# optoisolator-shield.net
KiCad netlist of a schematic drawn in EAGLE
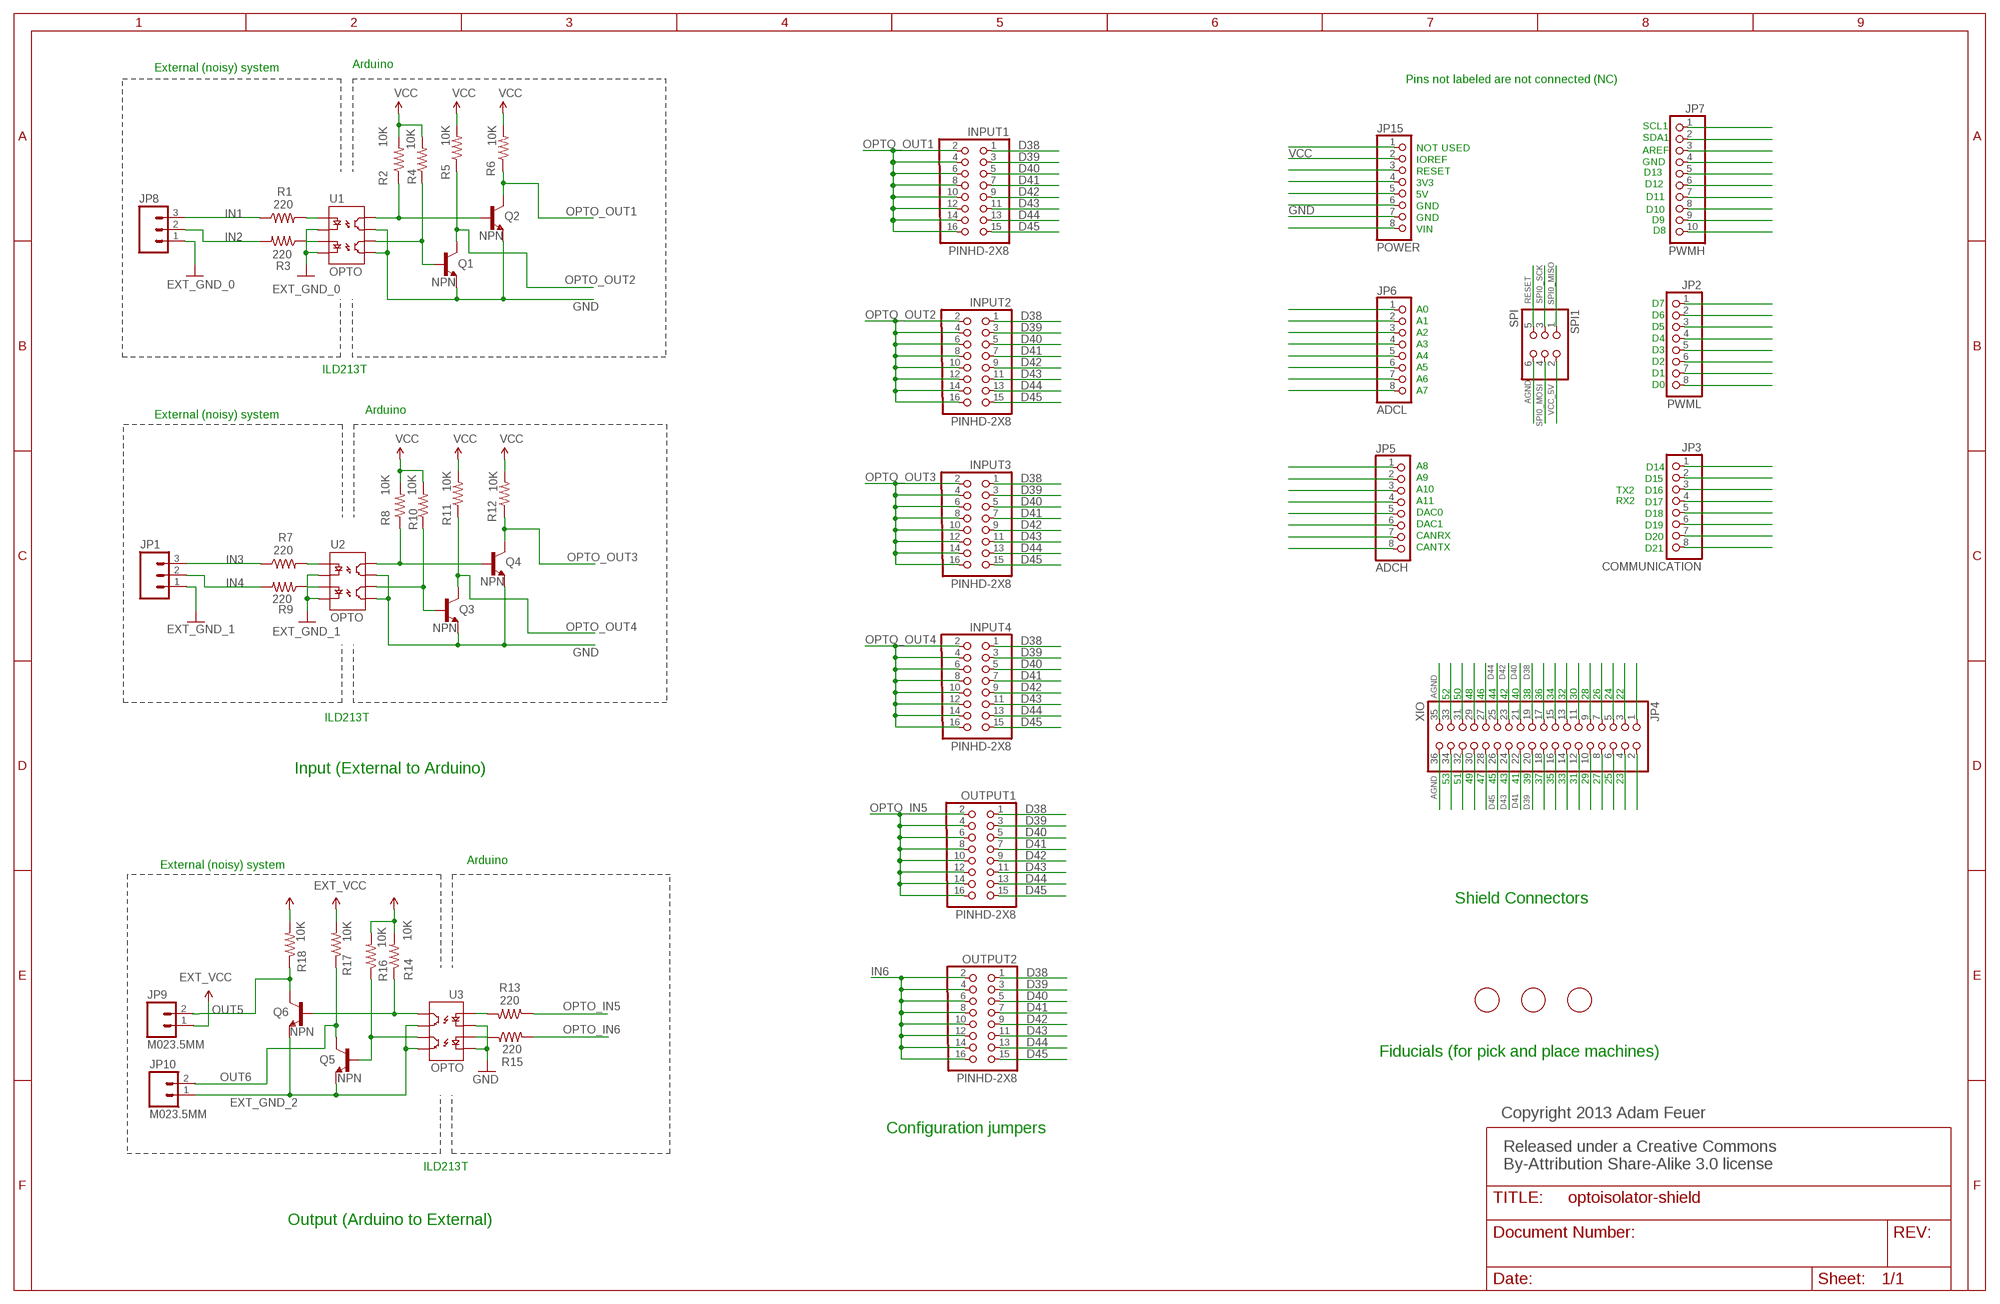
[diagram p0: schematic, sheet 1]

(export (version "E")
  (design (tool "Eeschema 10.0.6"))
  (components
    (comp (ref "INPUT1")
      (value "PINHD-2X8")
      (footprint "eagle-import:2X08")
      (libsource (lib "eagle-import") (part "PINHD-2X8"))
    )
    (comp (ref "INPUT2")
      (value "PINHD-2X8")
      (footprint "eagle-import:2X08")
      (libsource (lib "eagle-import") (part "PINHD-2X8"))
    )
    (comp (ref "INPUT3")
      (value "PINHD-2X8")
      (footprint "eagle-import:2X08")
      (libsource (lib "eagle-import") (part "PINHD-2X8"))
    )
    (comp (ref "INPUT4")
      (value "PINHD-2X8")
      (footprint "eagle-import:2X08")
      (libsource (lib "eagle-import") (part "PINHD-2X8"))
    )
    (comp (ref "JP1")
      (value "M03SCREW")
      (footprint "eagle-import:SCREWTERMINAL-3.5MM-3")
      (libsource (lib "eagle-import") (part "M03SCREW"))
    )
    (comp (ref "JP2")
      (value "PWML")
      (footprint "eagle-import:1X08")
      (libsource (lib "eagle-import") (part "PINHD-1X8"))
    )
    (comp (ref "JP3")
      (value "COMMUNICATION")
      (footprint "eagle-import:1X08")
      (libsource (lib "eagle-import") (part "PINHD-1X8"))
    )
    (comp (ref "JP4")
      (value "XIO")
      (footprint "eagle-import:2X18")
      (libsource (lib "eagle-import") (part "PINHD-2X18"))
    )
    (comp (ref "JP5")
      (value "ADCH")
      (footprint "eagle-import:1X08")
      (libsource (lib "eagle-import") (part "PINHD-1X8"))
    )
    (comp (ref "JP6")
      (value "ADCL")
      (footprint "eagle-import:1X08")
      (libsource (lib "eagle-import") (part "PINHD-1X8"))
    )
    (comp (ref "JP7")
      (value "PWMH")
      (footprint "eagle-import:1X10")
      (libsource (lib "eagle-import") (part "PINHD-1X10"))
    )
    (comp (ref "JP8")
      (value "M03SCREW")
      (footprint "eagle-import:SCREWTERMINAL-3.5MM-3")
      (libsource (lib "eagle-import") (part "M03SCREW"))
    )
    (comp (ref "JP9")
      (value "M023.5MM")
      (footprint "eagle-import:SCREWTERMINAL-3.5MM-2")
      (libsource (lib "eagle-import") (part "M023.5MM"))
    )
    (comp (ref "JP10")
      (value "M023.5MM")
      (footprint "eagle-import:SCREWTERMINAL-3.5MM-2")
      (libsource (lib "eagle-import") (part "M023.5MM"))
    )
    (comp (ref "JP15")
      (value "POWER")
      (footprint "eagle-import:1X08")
      (libsource (lib "eagle-import") (part "PINHD-1X8"))
    )
    (comp (ref "OUTPUT1")
      (value "PINHD-2X8")
      (footprint "eagle-import:2X08")
      (libsource (lib "eagle-import") (part "PINHD-2X8"))
    )
    (comp (ref "OUTPUT2")
      (value "PINHD-2X8")
      (footprint "eagle-import:2X08")
      (libsource (lib "eagle-import") (part "PINHD-2X8"))
    )
    (comp (ref "Q1")
      (value "NPN")
      (footprint "eagle-import:SOT23-3")
      (libsource (lib "eagle-import") (part "TRANSISTOR_NPNSOT23-3"))
    )
    (comp (ref "Q2")
      (value "NPN")
      (footprint "eagle-import:SOT23-3")
      (libsource (lib "eagle-import") (part "TRANSISTOR_NPNSOT23-3"))
    )
    (comp (ref "Q3")
      (value "NPN")
      (footprint "eagle-import:SOT23-3")
      (libsource (lib "eagle-import") (part "TRANSISTOR_NPNSOT23-3"))
    )
    (comp (ref "Q4")
      (value "NPN")
      (footprint "eagle-import:SOT23-3")
      (libsource (lib "eagle-import") (part "TRANSISTOR_NPNSOT23-3"))
    )
    (comp (ref "Q5")
      (value "NPN")
      (footprint "eagle-import:SOT23-3")
      (libsource (lib "eagle-import") (part "TRANSISTOR_NPNSOT23-3"))
    )
    (comp (ref "Q6")
      (value "NPN")
      (footprint "eagle-import:SOT23-3")
      (libsource (lib "eagle-import") (part "TRANSISTOR_NPNSOT23-3"))
    )
    (comp (ref "R1")
      (value "220")
      (footprint "eagle-import:C0402")
      (libsource (lib "eagle-import") (part "RESISTOR0402"))
    )
    (comp (ref "R2")
      (value "10K")
      (footprint "eagle-import:C0402")
      (libsource (lib "eagle-import") (part "RESISTOR0402"))
    )
    (comp (ref "R3")
      (value "220")
      (footprint "eagle-import:C0402")
      (libsource (lib "eagle-import") (part "RESISTOR0402"))
    )
    (comp (ref "R4")
      (value "10K")
      (footprint "eagle-import:C0402")
      (libsource (lib "eagle-import") (part "RESISTOR0402"))
    )
    (comp (ref "R5")
      (value "10K")
      (footprint "eagle-import:C0402")
      (libsource (lib "eagle-import") (part "RESISTOR0402"))
    )
    (comp (ref "R6")
      (value "10K")
      (footprint "eagle-import:C0402")
      (libsource (lib "eagle-import") (part "RESISTOR0402"))
    )
    (comp (ref "R7")
      (value "220")
      (footprint "eagle-import:C0402")
      (libsource (lib "eagle-import") (part "RESISTOR0402"))
    )
    (comp (ref "R8")
      (value "10K")
      (footprint "eagle-import:C0402")
      (libsource (lib "eagle-import") (part "RESISTOR0402"))
    )
    (comp (ref "R9")
      (value "220")
      (footprint "eagle-import:C0402")
      (libsource (lib "eagle-import") (part "RESISTOR0402"))
    )
    (comp (ref "R10")
      (value "10K")
      (footprint "eagle-import:C0402")
      (libsource (lib "eagle-import") (part "RESISTOR0402"))
    )
    (comp (ref "R11")
      (value "10K")
      (footprint "eagle-import:C0402")
      (libsource (lib "eagle-import") (part "RESISTOR0402"))
    )
    (comp (ref "R12")
      (value "10K")
      (footprint "eagle-import:C0402")
      (libsource (lib "eagle-import") (part "RESISTOR0402"))
    )
    (comp (ref "R13")
      (value "220")
      (footprint "eagle-import:C0402")
      (libsource (lib "eagle-import") (part "RESISTOR0402"))
    )
    (comp (ref "R14")
      (value "10K")
      (footprint "eagle-import:C0402")
      (libsource (lib "eagle-import") (part "RESISTOR0402"))
    )
    (comp (ref "R15")
      (value "220")
      (footprint "eagle-import:C0402")
      (libsource (lib "eagle-import") (part "RESISTOR0402"))
    )
    (comp (ref "R16")
      (value "10K")
      (footprint "eagle-import:C0402")
      (libsource (lib "eagle-import") (part "RESISTOR0402"))
    )
    (comp (ref "R17")
      (value "10K")
      (footprint "eagle-import:C0402")
      (libsource (lib "eagle-import") (part "RESISTOR0402"))
    )
    (comp (ref "R18")
      (value "10K")
      (footprint "eagle-import:C0402")
      (libsource (lib "eagle-import") (part "RESISTOR0402"))
    )
    (comp (ref "SPI1")
      (value "SPI")
      (footprint "eagle-import:2X03")
      (libsource (lib "eagle-import") (part "PINHD-2X3"))
    )
    (comp (ref "U$2")
      (value "FIDUCIAL")
      (footprint "eagle-import:FIDUCIAL_1MM")
      (libsource (lib "eagle-import") (part "FIDUCIAL"))
    )
    (comp (ref "U$5")
      (value "FIDUCIAL")
      (footprint "eagle-import:FIDUCIAL_1MM")
      (libsource (lib "eagle-import") (part "FIDUCIAL"))
    )
    (comp (ref "U$6")
      (value "FIDUCIAL")
      (footprint "eagle-import:FIDUCIAL_1MM")
      (libsource (lib "eagle-import") (part "FIDUCIAL"))
    )
    (comp (ref "U1")
      (value "OPTO")
      (footprint "eagle-import:SO08-2")
      (libsource (lib "eagle-import") (part "OPTOISOLATOR-2SOIC8"))
    )
    (comp (ref "U2")
      (value "OPTO")
      (footprint "eagle-import:SO08-2")
      (libsource (lib "eagle-import") (part "OPTOISOLATOR-2SOIC8"))
    )
    (comp (ref "U3")
      (value "OPTO")
      (footprint "eagle-import:SO08-2")
      (libsource (lib "eagle-import") (part "OPTOISOLATOR-2SOIC8"))
    )
  )
  (nets
    (net (code "1") (name "/AGND") (class "Default")
      (node (ref "JP4") (pin "35") (pinfunction "35_35") (pintype "passive"))
      (node (ref "JP4") (pin "36") (pinfunction "36_36") (pintype "passive"))
      (node (ref "SPI1") (pin "6") (pinfunction "6_6") (pintype "passive"))
    )
    (net (code "2") (name "/D38") (class "Default")
      (node (ref "INPUT1") (pin "1") (pinfunction "1_1") (pintype "passive"))
      (node (ref "INPUT2") (pin "1") (pinfunction "1_1") (pintype "passive"))
      (node (ref "INPUT3") (pin "1") (pinfunction "1_1") (pintype "passive"))
      (node (ref "INPUT4") (pin "1") (pinfunction "1_1") (pintype "passive"))
      (node (ref "JP4") (pin "19") (pinfunction "19_19") (pintype "passive"))
      (node (ref "OUTPUT1") (pin "1") (pinfunction "1_1") (pintype "passive"))
      (node (ref "OUTPUT2") (pin "1") (pinfunction "1_1") (pintype "passive"))
    )
    (net (code "3") (name "/D39") (class "Default")
      (node (ref "INPUT1") (pin "3") (pinfunction "3_3") (pintype "passive"))
      (node (ref "INPUT2") (pin "3") (pinfunction "3_3") (pintype "passive"))
      (node (ref "INPUT3") (pin "3") (pinfunction "3_3") (pintype "passive"))
      (node (ref "INPUT4") (pin "3") (pinfunction "3_3") (pintype "passive"))
      (node (ref "JP4") (pin "20") (pinfunction "20_20") (pintype "passive"))
      (node (ref "OUTPUT1") (pin "3") (pinfunction "3_3") (pintype "passive"))
      (node (ref "OUTPUT2") (pin "3") (pinfunction "3_3") (pintype "passive"))
    )
    (net (code "4") (name "/D40") (class "Default")
      (node (ref "INPUT1") (pin "5") (pinfunction "5_5") (pintype "passive"))
      (node (ref "INPUT2") (pin "5") (pinfunction "5_5") (pintype "passive"))
      (node (ref "INPUT3") (pin "5") (pinfunction "5_5") (pintype "passive"))
      (node (ref "INPUT4") (pin "5") (pinfunction "5_5") (pintype "passive"))
      (node (ref "JP4") (pin "21") (pinfunction "21_21") (pintype "passive"))
      (node (ref "OUTPUT1") (pin "5") (pinfunction "5_5") (pintype "passive"))
      (node (ref "OUTPUT2") (pin "5") (pinfunction "5_5") (pintype "passive"))
    )
    (net (code "5") (name "/D41") (class "Default")
      (node (ref "INPUT1") (pin "7") (pinfunction "7_7") (pintype "passive"))
      (node (ref "INPUT2") (pin "7") (pinfunction "7_7") (pintype "passive"))
      (node (ref "INPUT3") (pin "7") (pinfunction "7_7") (pintype "passive"))
      (node (ref "INPUT4") (pin "7") (pinfunction "7_7") (pintype "passive"))
      (node (ref "JP4") (pin "22") (pinfunction "22_22") (pintype "passive"))
      (node (ref "OUTPUT1") (pin "7") (pinfunction "7_7") (pintype "passive"))
      (node (ref "OUTPUT2") (pin "7") (pinfunction "7_7") (pintype "passive"))
    )
    (net (code "6") (name "/D42") (class "Default")
      (node (ref "INPUT1") (pin "9") (pinfunction "9_9") (pintype "passive"))
      (node (ref "INPUT2") (pin "9") (pinfunction "9_9") (pintype "passive"))
      (node (ref "INPUT3") (pin "9") (pinfunction "9_9") (pintype "passive"))
      (node (ref "INPUT4") (pin "9") (pinfunction "9_9") (pintype "passive"))
      (node (ref "JP4") (pin "23") (pinfunction "23_23") (pintype "passive"))
      (node (ref "OUTPUT1") (pin "9") (pinfunction "9_9") (pintype "passive"))
      (node (ref "OUTPUT2") (pin "9") (pinfunction "9_9") (pintype "passive"))
    )
    (net (code "7") (name "/D43") (class "Default")
      (node (ref "INPUT1") (pin "11") (pinfunction "11_11") (pintype "passive"))
      (node (ref "INPUT2") (pin "11") (pinfunction "11_11") (pintype "passive"))
      (node (ref "INPUT3") (pin "11") (pinfunction "11_11") (pintype "passive"))
      (node (ref "INPUT4") (pin "11") (pinfunction "11_11") (pintype "passive"))
      (node (ref "JP4") (pin "24") (pinfunction "24_24") (pintype "passive"))
      (node (ref "OUTPUT1") (pin "11") (pinfunction "11_11") (pintype "passive"))
      (node (ref "OUTPUT2") (pin "11") (pinfunction "11_11") (pintype "passive"))
    )
    (net (code "8") (name "/D44") (class "Default")
      (node (ref "INPUT1") (pin "13") (pinfunction "13_13") (pintype "passive"))
      (node (ref "INPUT2") (pin "13") (pinfunction "13_13") (pintype "passive"))
      (node (ref "INPUT3") (pin "13") (pinfunction "13_13") (pintype "passive"))
      (node (ref "INPUT4") (pin "13") (pinfunction "13_13") (pintype "passive"))
      (node (ref "JP4") (pin "25") (pinfunction "25_25") (pintype "passive"))
      (node (ref "OUTPUT1") (pin "13") (pinfunction "13_13") (pintype "passive"))
      (node (ref "OUTPUT2") (pin "13") (pinfunction "13_13") (pintype "passive"))
    )
    (net (code "9") (name "/D45") (class "Default")
      (node (ref "INPUT1") (pin "15") (pinfunction "15_15") (pintype "passive"))
      (node (ref "INPUT2") (pin "15") (pinfunction "15_15") (pintype "passive"))
      (node (ref "INPUT3") (pin "15") (pinfunction "15_15") (pintype "passive"))
      (node (ref "INPUT4") (pin "15") (pinfunction "15_15") (pintype "passive"))
      (node (ref "JP4") (pin "26") (pinfunction "26_26") (pintype "passive"))
      (node (ref "OUTPUT1") (pin "15") (pinfunction "15_15") (pintype "passive"))
      (node (ref "OUTPUT2") (pin "15") (pinfunction "15_15") (pintype "passive"))
    )
    (net (code "10") (name "/EXT_GND_2") (class "Default")
      (node (ref "JP10") (pin "1") (pinfunction "1_1") (pintype "passive"))
      (node (ref "Q5") (pin "2") (pinfunction "E_2") (pintype "passive"))
      (node (ref "Q6") (pin "2") (pinfunction "E_2") (pintype "passive"))
      (node (ref "U3") (pin "5") (pinfunction "EM2_5") (pintype "bidirectional"))
      (node (ref "U3") (pin "7") (pinfunction "EM1_7") (pintype "bidirectional"))
    )
    (net (code "11") (name "/IN1") (class "Default")
      (node (ref "JP8") (pin "3") (pinfunction "3_3") (pintype "passive"))
      (node (ref "R1") (pin "1") (pinfunction "1_1") (pintype "passive"))
    )
    (net (code "12") (name "/IN2") (class "Default")
      (node (ref "JP8") (pin "2") (pinfunction "2_2") (pintype "passive"))
      (node (ref "R3") (pin "2") (pinfunction "2_2") (pintype "passive"))
    )
    (net (code "13") (name "/IN3") (class "Default")
      (node (ref "JP1") (pin "3") (pinfunction "3_3") (pintype "passive"))
      (node (ref "R7") (pin "1") (pinfunction "1_1") (pintype "passive"))
    )
    (net (code "14") (name "/IN4") (class "Default")
      (node (ref "JP1") (pin "2") (pinfunction "2_2") (pintype "passive"))
      (node (ref "R9") (pin "2") (pinfunction "2_2") (pintype "passive"))
    )
    (net (code "15") (name "/IN6") (class "Default")
      (node (ref "OUTPUT2") (pin "10") (pinfunction "10_10") (pintype "passive"))
      (node (ref "OUTPUT2") (pin "12") (pinfunction "12_12") (pintype "passive"))
      (node (ref "OUTPUT2") (pin "14") (pinfunction "14_14") (pintype "passive"))
      (node (ref "OUTPUT2") (pin "16") (pinfunction "16_16") (pintype "passive"))
      (node (ref "OUTPUT2") (pin "2") (pinfunction "2_2") (pintype "passive"))
      (node (ref "OUTPUT2") (pin "4") (pinfunction "4_4") (pintype "passive"))
      (node (ref "OUTPUT2") (pin "6") (pinfunction "6_6") (pintype "passive"))
      (node (ref "OUTPUT2") (pin "8") (pinfunction "8_8") (pintype "passive"))
    )
    (net (code "16") (name "/OPTO_IN5") (class "Default")
      (node (ref "OUTPUT1") (pin "10") (pinfunction "10_10") (pintype "passive"))
      (node (ref "OUTPUT1") (pin "12") (pinfunction "12_12") (pintype "passive"))
      (node (ref "OUTPUT1") (pin "14") (pinfunction "14_14") (pintype "passive"))
      (node (ref "OUTPUT1") (pin "16") (pinfunction "16_16") (pintype "passive"))
      (node (ref "OUTPUT1") (pin "2") (pinfunction "2_2") (pintype "passive"))
      (node (ref "OUTPUT1") (pin "4") (pinfunction "4_4") (pintype "passive"))
      (node (ref "OUTPUT1") (pin "6") (pinfunction "6_6") (pintype "passive"))
      (node (ref "OUTPUT1") (pin "8") (pinfunction "8_8") (pintype "passive"))
      (node (ref "R13") (pin "1") (pinfunction "1_1") (pintype "passive"))
    )
    (net (code "17") (name "/OPTO_IN6") (class "Default")
      (node (ref "R15") (pin "2") (pinfunction "2_2") (pintype "passive"))
    )
    (net (code "18") (name "/OPTO_OUT1") (class "Default")
      (node (ref "INPUT1") (pin "10") (pinfunction "10_10") (pintype "passive"))
      (node (ref "INPUT1") (pin "12") (pinfunction "12_12") (pintype "passive"))
      (node (ref "INPUT1") (pin "14") (pinfunction "14_14") (pintype "passive"))
      (node (ref "INPUT1") (pin "16") (pinfunction "16_16") (pintype "passive"))
      (node (ref "INPUT1") (pin "2") (pinfunction "2_2") (pintype "passive"))
      (node (ref "INPUT1") (pin "4") (pinfunction "4_4") (pintype "passive"))
      (node (ref "INPUT1") (pin "6") (pinfunction "6_6") (pintype "passive"))
      (node (ref "INPUT1") (pin "8") (pinfunction "8_8") (pintype "passive"))
      (node (ref "Q2") (pin "3") (pinfunction "C_3") (pintype "passive"))
      (node (ref "R6") (pin "1") (pinfunction "1_1") (pintype "passive"))
    )
    (net (code "19") (name "/OPTO_OUT2") (class "Default")
      (node (ref "INPUT2") (pin "10") (pinfunction "10_10") (pintype "passive"))
      (node (ref "INPUT2") (pin "12") (pinfunction "12_12") (pintype "passive"))
      (node (ref "INPUT2") (pin "14") (pinfunction "14_14") (pintype "passive"))
      (node (ref "INPUT2") (pin "16") (pinfunction "16_16") (pintype "passive"))
      (node (ref "INPUT2") (pin "2") (pinfunction "2_2") (pintype "passive"))
      (node (ref "INPUT2") (pin "4") (pinfunction "4_4") (pintype "passive"))
      (node (ref "INPUT2") (pin "6") (pinfunction "6_6") (pintype "passive"))
      (node (ref "INPUT2") (pin "8") (pinfunction "8_8") (pintype "passive"))
      (node (ref "Q1") (pin "3") (pinfunction "C_3") (pintype "passive"))
      (node (ref "R5") (pin "1") (pinfunction "1_1") (pintype "passive"))
    )
    (net (code "20") (name "/OPTO_OUT3") (class "Default")
      (node (ref "INPUT3") (pin "10") (pinfunction "10_10") (pintype "passive"))
      (node (ref "INPUT3") (pin "12") (pinfunction "12_12") (pintype "passive"))
      (node (ref "INPUT3") (pin "14") (pinfunction "14_14") (pintype "passive"))
      (node (ref "INPUT3") (pin "16") (pinfunction "16_16") (pintype "passive"))
      (node (ref "INPUT3") (pin "2") (pinfunction "2_2") (pintype "passive"))
      (node (ref "INPUT3") (pin "4") (pinfunction "4_4") (pintype "passive"))
      (node (ref "INPUT3") (pin "6") (pinfunction "6_6") (pintype "passive"))
      (node (ref "INPUT3") (pin "8") (pinfunction "8_8") (pintype "passive"))
      (node (ref "Q4") (pin "3") (pinfunction "C_3") (pintype "passive"))
      (node (ref "R12") (pin "1") (pinfunction "1_1") (pintype "passive"))
    )
    (net (code "21") (name "/OPTO_OUT4") (class "Default")
      (node (ref "INPUT4") (pin "10") (pinfunction "10_10") (pintype "passive"))
      (node (ref "INPUT4") (pin "12") (pinfunction "12_12") (pintype "passive"))
      (node (ref "INPUT4") (pin "14") (pinfunction "14_14") (pintype "passive"))
      (node (ref "INPUT4") (pin "16") (pinfunction "16_16") (pintype "passive"))
      (node (ref "INPUT4") (pin "2") (pinfunction "2_2") (pintype "passive"))
      (node (ref "INPUT4") (pin "4") (pinfunction "4_4") (pintype "passive"))
      (node (ref "INPUT4") (pin "6") (pinfunction "6_6") (pintype "passive"))
      (node (ref "INPUT4") (pin "8") (pinfunction "8_8") (pintype "passive"))
      (node (ref "Q3") (pin "3") (pinfunction "C_3") (pintype "passive"))
      (node (ref "R11") (pin "1") (pinfunction "1_1") (pintype "passive"))
    )
    (net (code "22") (name "/OUT5") (class "Default")
      (node (ref "Q6") (pin "3") (pinfunction "C_3") (pintype "passive"))
      (node (ref "R18") (pin "1") (pinfunction "1_1") (pintype "passive"))
    )
    (net (code "23") (name "/OUT6") (class "Default")
      (node (ref "Q5") (pin "3") (pinfunction "C_3") (pintype "passive"))
      (node (ref "R17") (pin "1") (pinfunction "1_1") (pintype "passive"))
    )
    (net (code "24") (name "/RESET") (class "Default")
      (node (ref "SPI1") (pin "5") (pinfunction "5_5") (pintype "passive"))
    )
    (net (code "25") (name "/SPI0_MISO") (class "Default")
      (node (ref "SPI1") (pin "1") (pinfunction "1_1") (pintype "passive"))
    )
    (net (code "26") (name "/SPI0_MOSI") (class "Default")
      (node (ref "SPI1") (pin "4") (pinfunction "4_4") (pintype "passive"))
    )
    (net (code "27") (name "/SPI0_SCK") (class "Default")
      (node (ref "SPI1") (pin "3") (pinfunction "3_3") (pintype "passive"))
    )
    (net (code "28") (name "/VCC_5V") (class "Default")
      (node (ref "SPI1") (pin "2") (pinfunction "2_2") (pintype "passive"))
    )
    (net (code "29") (name "EXTERNAL_VCC") (class "Default")
      (node (ref "JP9") (pin "1") (pinfunction "1_1") (pintype "passive"))
      (node (ref "R14") (pin "2") (pinfunction "2_2") (pintype "passive"))
      (node (ref "R16") (pin "2") (pinfunction "2_2") (pintype "passive"))
      (node (ref "R17") (pin "2") (pinfunction "2_2") (pintype "passive"))
      (node (ref "R18") (pin "2") (pinfunction "2_2") (pintype "passive"))
    )
    (net (code "30") (name "EXT_GND_0") (class "Default")
      (node (ref "JP8") (pin "1") (pinfunction "1_1") (pintype "passive"))
      (node (ref "U1") (pin "2") (pinfunction "C1_2") (pintype "bidirectional"))
      (node (ref "U1") (pin "4") (pinfunction "C2_4") (pintype "bidirectional"))
    )
    (net (code "31") (name "EXT_GND_1") (class "Default")
      (node (ref "JP1") (pin "1") (pinfunction "1_1") (pintype "passive"))
      (node (ref "U2") (pin "2") (pinfunction "C1_2") (pintype "bidirectional"))
      (node (ref "U2") (pin "4") (pinfunction "C2_4") (pintype "bidirectional"))
    )
    (net (code "32") (name "GND") (class "Default")
      (node (ref "JP15") (pin "7") (pinfunction "7_7") (pintype "passive"))
      (node (ref "Q1") (pin "2") (pinfunction "E_2") (pintype "passive"))
      (node (ref "Q2") (pin "2") (pinfunction "E_2") (pintype "passive"))
      (node (ref "Q3") (pin "2") (pinfunction "E_2") (pintype "passive"))
      (node (ref "Q4") (pin "2") (pinfunction "E_2") (pintype "passive"))
      (node (ref "U1") (pin "5") (pinfunction "EM2_5") (pintype "bidirectional"))
      (node (ref "U1") (pin "7") (pinfunction "EM1_7") (pintype "bidirectional"))
      (node (ref "U2") (pin "5") (pinfunction "EM2_5") (pintype "bidirectional"))
      (node (ref "U2") (pin "7") (pinfunction "EM1_7") (pintype "bidirectional"))
      (node (ref "U3") (pin "2") (pinfunction "C1_2") (pintype "bidirectional"))
      (node (ref "U3") (pin "4") (pinfunction "C2_4") (pintype "bidirectional"))
    )
    (net (code "33") (name "Net-(Q1-B)") (class "Default")
      (node (ref "Q1") (pin "1") (pinfunction "B_1") (pintype "passive"))
      (node (ref "R4") (pin "1") (pinfunction "1_1") (pintype "passive"))
      (node (ref "U1") (pin "6") (pinfunction "CL2_6") (pintype "bidirectional"))
    )
    (net (code "34") (name "Net-(Q2-B)") (class "Default")
      (node (ref "Q2") (pin "1") (pinfunction "B_1") (pintype "passive"))
      (node (ref "R2") (pin "1") (pinfunction "1_1") (pintype "passive"))
      (node (ref "U1") (pin "8") (pinfunction "CL1_8") (pintype "bidirectional"))
    )
    (net (code "35") (name "Net-(Q3-B)") (class "Default")
      (node (ref "Q3") (pin "1") (pinfunction "B_1") (pintype "passive"))
      (node (ref "R10") (pin "1") (pinfunction "1_1") (pintype "passive"))
      (node (ref "U2") (pin "6") (pinfunction "CL2_6") (pintype "bidirectional"))
    )
    (net (code "36") (name "Net-(Q4-B)") (class "Default")
      (node (ref "Q4") (pin "1") (pinfunction "B_1") (pintype "passive"))
      (node (ref "R8") (pin "1") (pinfunction "1_1") (pintype "passive"))
      (node (ref "U2") (pin "8") (pinfunction "CL1_8") (pintype "bidirectional"))
    )
    (net (code "37") (name "Net-(Q5-B)") (class "Default")
      (node (ref "Q5") (pin "1") (pinfunction "B_1") (pintype "passive"))
      (node (ref "R16") (pin "1") (pinfunction "1_1") (pintype "passive"))
      (node (ref "U3") (pin "6") (pinfunction "CL2_6") (pintype "bidirectional"))
    )
    (net (code "38") (name "Net-(Q6-B)") (class "Default")
      (node (ref "Q6") (pin "1") (pinfunction "B_1") (pintype "passive"))
      (node (ref "R14") (pin "1") (pinfunction "1_1") (pintype "passive"))
      (node (ref "U3") (pin "8") (pinfunction "CL1_8") (pintype "bidirectional"))
    )
    (net (code "39") (name "Net-(U1-A1)") (class "Default")
      (node (ref "R1") (pin "2") (pinfunction "2_2") (pintype "passive"))
      (node (ref "U1") (pin "1") (pinfunction "A1_1") (pintype "bidirectional"))
    )
    (net (code "40") (name "Net-(U1-A2)") (class "Default")
      (node (ref "R3") (pin "1") (pinfunction "1_1") (pintype "passive"))
      (node (ref "U1") (pin "3") (pinfunction "A2_3") (pintype "bidirectional"))
    )
    (net (code "41") (name "Net-(U2-A1)") (class "Default")
      (node (ref "R7") (pin "2") (pinfunction "2_2") (pintype "passive"))
      (node (ref "U2") (pin "1") (pinfunction "A1_1") (pintype "bidirectional"))
    )
    (net (code "42") (name "Net-(U2-A2)") (class "Default")
      (node (ref "R9") (pin "1") (pinfunction "1_1") (pintype "passive"))
      (node (ref "U2") (pin "3") (pinfunction "A2_3") (pintype "bidirectional"))
    )
    (net (code "43") (name "Net-(U3-A1)") (class "Default")
      (node (ref "R13") (pin "2") (pinfunction "2_2") (pintype "passive"))
      (node (ref "U3") (pin "1") (pinfunction "A1_1") (pintype "bidirectional"))
    )
    (net (code "44") (name "Net-(U3-A2)") (class "Default")
      (node (ref "R15") (pin "1") (pinfunction "1_1") (pintype "passive"))
      (node (ref "U3") (pin "3") (pinfunction "A2_3") (pintype "bidirectional"))
    )
    (net (code "45") (name "VCC") (class "Default")
      (node (ref "JP15") (pin "2") (pinfunction "2_2") (pintype "passive"))
      (node (ref "R10") (pin "2") (pinfunction "2_2") (pintype "passive"))
      (node (ref "R11") (pin "2") (pinfunction "2_2") (pintype "passive"))
      (node (ref "R12") (pin "2") (pinfunction "2_2") (pintype "passive"))
      (node (ref "R2") (pin "2") (pinfunction "2_2") (pintype "passive"))
      (node (ref "R4") (pin "2") (pinfunction "2_2") (pintype "passive"))
      (node (ref "R5") (pin "2") (pinfunction "2_2") (pintype "passive"))
      (node (ref "R6") (pin "2") (pinfunction "2_2") (pintype "passive"))
      (node (ref "R8") (pin "2") (pinfunction "2_2") (pintype "passive"))
    )
    (net (code "46") (name "unconnected-(JP2-Pad1)") (class "Default")
      (node (ref "JP2") (pin "1") (pinfunction "1_1") (pintype "passive"))
    )
    (net (code "47") (name "unconnected-(JP2-Pad2)") (class "Default")
      (node (ref "JP2") (pin "2") (pinfunction "2_2") (pintype "passive"))
    )
    (net (code "48") (name "unconnected-(JP2-Pad3)") (class "Default")
      (node (ref "JP2") (pin "3") (pinfunction "3_3") (pintype "passive"))
    )
    (net (code "49") (name "unconnected-(JP2-Pad4)") (class "Default")
      (node (ref "JP2") (pin "4") (pinfunction "4_4") (pintype "passive"))
    )
    (net (code "50") (name "unconnected-(JP2-Pad5)") (class "Default")
      (node (ref "JP2") (pin "5") (pinfunction "5_5") (pintype "passive"))
    )
    (net (code "51") (name "unconnected-(JP2-Pad6)") (class "Default")
      (node (ref "JP2") (pin "6") (pinfunction "6_6") (pintype "passive"))
    )
    (net (code "52") (name "unconnected-(JP2-Pad7)") (class "Default")
      (node (ref "JP2") (pin "7") (pinfunction "7_7") (pintype "passive"))
    )
    (net (code "53") (name "unconnected-(JP2-Pad8)") (class "Default")
      (node (ref "JP2") (pin "8") (pinfunction "8_8") (pintype "passive"))
    )
    (net (code "54") (name "unconnected-(JP3-Pad1)") (class "Default")
      (node (ref "JP3") (pin "1") (pinfunction "1_1") (pintype "passive"))
    )
    (net (code "55") (name "unconnected-(JP3-Pad2)") (class "Default")
      (node (ref "JP3") (pin "2") (pinfunction "2_2") (pintype "passive"))
    )
    (net (code "56") (name "unconnected-(JP3-Pad3)") (class "Default")
      (node (ref "JP3") (pin "3") (pinfunction "3_3") (pintype "passive"))
    )
    (net (code "57") (name "unconnected-(JP3-Pad4)") (class "Default")
      (node (ref "JP3") (pin "4") (pinfunction "4_4") (pintype "passive"))
    )
    (net (code "58") (name "unconnected-(JP3-Pad5)") (class "Default")
      (node (ref "JP3") (pin "5") (pinfunction "5_5") (pintype "passive"))
    )
    (net (code "59") (name "unconnected-(JP3-Pad6)") (class "Default")
      (node (ref "JP3") (pin "6") (pinfunction "6_6") (pintype "passive"))
    )
    (net (code "60") (name "unconnected-(JP3-Pad7)") (class "Default")
      (node (ref "JP3") (pin "7") (pinfunction "7_7") (pintype "passive"))
    )
    (net (code "61") (name "unconnected-(JP3-Pad8)") (class "Default")
      (node (ref "JP3") (pin "8") (pinfunction "8_8") (pintype "passive"))
    )
    (net (code "62") (name "unconnected-(JP4-Pad1)") (class "Default")
      (node (ref "JP4") (pin "1") (pinfunction "1_1") (pintype "passive"))
    )
    (net (code "63") (name "unconnected-(JP4-Pad2)") (class "Default")
      (node (ref "JP4") (pin "2") (pinfunction "2_2") (pintype "passive"))
    )
    (net (code "64") (name "unconnected-(JP4-Pad3)") (class "Default")
      (node (ref "JP4") (pin "3") (pinfunction "3_3") (pintype "passive"))
    )
    (net (code "65") (name "unconnected-(JP4-Pad4)") (class "Default")
      (node (ref "JP4") (pin "4") (pinfunction "4_4") (pintype "passive"))
    )
    (net (code "66") (name "unconnected-(JP4-Pad5)") (class "Default")
      (node (ref "JP4") (pin "5") (pinfunction "5_5") (pintype "passive"))
    )
    (net (code "67") (name "unconnected-(JP4-Pad6)") (class "Default")
      (node (ref "JP4") (pin "6") (pinfunction "6_6") (pintype "passive"))
    )
    (net (code "68") (name "unconnected-(JP4-Pad7)") (class "Default")
      (node (ref "JP4") (pin "7") (pinfunction "7_7") (pintype "passive"))
    )
    (net (code "69") (name "unconnected-(JP4-Pad8)") (class "Default")
      (node (ref "JP4") (pin "8") (pinfunction "8_8") (pintype "passive"))
    )
    (net (code "70") (name "unconnected-(JP4-Pad9)") (class "Default")
      (node (ref "JP4") (pin "9") (pinfunction "9_9") (pintype "passive"))
    )
    (net (code "71") (name "unconnected-(JP4-Pad10)") (class "Default")
      (node (ref "JP4") (pin "10") (pinfunction "10_10") (pintype "passive"))
    )
    (net (code "72") (name "unconnected-(JP4-Pad11)") (class "Default")
      (node (ref "JP4") (pin "11") (pinfunction "11_11") (pintype "passive"))
    )
    (net (code "73") (name "unconnected-(JP4-Pad12)") (class "Default")
      (node (ref "JP4") (pin "12") (pinfunction "12_12") (pintype "passive"))
    )
    (net (code "74") (name "unconnected-(JP4-Pad13)") (class "Default")
      (node (ref "JP4") (pin "13") (pinfunction "13_13") (pintype "passive"))
    )
    (net (code "75") (name "unconnected-(JP4-Pad14)") (class "Default")
      (node (ref "JP4") (pin "14") (pinfunction "14_14") (pintype "passive"))
    )
    (net (code "76") (name "unconnected-(JP4-Pad15)") (class "Default")
      (node (ref "JP4") (pin "15") (pinfunction "15_15") (pintype "passive"))
    )
    (net (code "77") (name "unconnected-(JP4-Pad16)") (class "Default")
      (node (ref "JP4") (pin "16") (pinfunction "16_16") (pintype "passive"))
    )
    (net (code "78") (name "unconnected-(JP4-Pad17)") (class "Default")
      (node (ref "JP4") (pin "17") (pinfunction "17_17") (pintype "passive"))
    )
    (net (code "79") (name "unconnected-(JP4-Pad18)") (class "Default")
      (node (ref "JP4") (pin "18") (pinfunction "18_18") (pintype "passive"))
    )
    (net (code "80") (name "unconnected-(JP4-Pad27)") (class "Default")
      (node (ref "JP4") (pin "27") (pinfunction "27_27") (pintype "passive"))
    )
    (net (code "81") (name "unconnected-(JP4-Pad28)") (class "Default")
      (node (ref "JP4") (pin "28") (pinfunction "28_28") (pintype "passive"))
    )
    (net (code "82") (name "unconnected-(JP4-Pad29)") (class "Default")
      (node (ref "JP4") (pin "29") (pinfunction "29_29") (pintype "passive"))
    )
    (net (code "83") (name "unconnected-(JP4-Pad30)") (class "Default")
      (node (ref "JP4") (pin "30") (pinfunction "30_30") (pintype "passive"))
    )
    (net (code "84") (name "unconnected-(JP4-Pad31)") (class "Default")
      (node (ref "JP4") (pin "31") (pinfunction "31_31") (pintype "passive"))
    )
    (net (code "85") (name "unconnected-(JP4-Pad32)") (class "Default")
      (node (ref "JP4") (pin "32") (pinfunction "32_32") (pintype "passive"))
    )
    (net (code "86") (name "unconnected-(JP4-Pad33)") (class "Default")
      (node (ref "JP4") (pin "33") (pinfunction "33_33") (pintype "passive"))
    )
    (net (code "87") (name "unconnected-(JP4-Pad34)") (class "Default")
      (node (ref "JP4") (pin "34") (pinfunction "34_34") (pintype "passive"))
    )
    (net (code "88") (name "unconnected-(JP5-Pad1)") (class "Default")
      (node (ref "JP5") (pin "1") (pinfunction "1_1") (pintype "passive"))
    )
    (net (code "89") (name "unconnected-(JP5-Pad2)") (class "Default")
      (node (ref "JP5") (pin "2") (pinfunction "2_2") (pintype "passive"))
    )
    (net (code "90") (name "unconnected-(JP5-Pad3)") (class "Default")
      (node (ref "JP5") (pin "3") (pinfunction "3_3") (pintype "passive"))
    )
    (net (code "91") (name "unconnected-(JP5-Pad4)") (class "Default")
      (node (ref "JP5") (pin "4") (pinfunction "4_4") (pintype "passive"))
    )
    (net (code "92") (name "unconnected-(JP5-Pad5)") (class "Default")
      (node (ref "JP5") (pin "5") (pinfunction "5_5") (pintype "passive"))
    )
    (net (code "93") (name "unconnected-(JP5-Pad6)") (class "Default")
      (node (ref "JP5") (pin "6") (pinfunction "6_6") (pintype "passive"))
    )
    (net (code "94") (name "unconnected-(JP5-Pad7)") (class "Default")
      (node (ref "JP5") (pin "7") (pinfunction "7_7") (pintype "passive"))
    )
    (net (code "95") (name "unconnected-(JP5-Pad8)") (class "Default")
      (node (ref "JP5") (pin "8") (pinfunction "8_8") (pintype "passive"))
    )
    (net (code "96") (name "unconnected-(JP6-Pad1)") (class "Default")
      (node (ref "JP6") (pin "1") (pinfunction "1_1") (pintype "passive"))
    )
    (net (code "97") (name "unconnected-(JP6-Pad2)") (class "Default")
      (node (ref "JP6") (pin "2") (pinfunction "2_2") (pintype "passive"))
    )
    (net (code "98") (name "unconnected-(JP6-Pad3)") (class "Default")
      (node (ref "JP6") (pin "3") (pinfunction "3_3") (pintype "passive"))
    )
    (net (code "99") (name "unconnected-(JP6-Pad4)") (class "Default")
      (node (ref "JP6") (pin "4") (pinfunction "4_4") (pintype "passive"))
    )
    (net (code "100") (name "unconnected-(JP6-Pad5)") (class "Default")
      (node (ref "JP6") (pin "5") (pinfunction "5_5") (pintype "passive"))
    )
    (net (code "101") (name "unconnected-(JP6-Pad6)") (class "Default")
      (node (ref "JP6") (pin "6") (pinfunction "6_6") (pintype "passive"))
    )
    (net (code "102") (name "unconnected-(JP6-Pad7)") (class "Default")
      (node (ref "JP6") (pin "7") (pinfunction "7_7") (pintype "passive"))
    )
    (net (code "103") (name "unconnected-(JP6-Pad8)") (class "Default")
      (node (ref "JP6") (pin "8") (pinfunction "8_8") (pintype "passive"))
    )
    (net (code "104") (name "unconnected-(JP7-Pad1)") (class "Default")
      (node (ref "JP7") (pin "1") (pinfunction "1_1") (pintype "passive"))
    )
    (net (code "105") (name "unconnected-(JP7-Pad2)") (class "Default")
      (node (ref "JP7") (pin "2") (pinfunction "2_2") (pintype "passive"))
    )
    (net (code "106") (name "unconnected-(JP7-Pad3)") (class "Default")
      (node (ref "JP7") (pin "3") (pinfunction "3_3") (pintype "passive"))
    )
    (net (code "107") (name "unconnected-(JP7-Pad4)") (class "Default")
      (node (ref "JP7") (pin "4") (pinfunction "4_4") (pintype "passive"))
    )
    (net (code "108") (name "unconnected-(JP7-Pad5)") (class "Default")
      (node (ref "JP7") (pin "5") (pinfunction "5_5") (pintype "passive"))
    )
    (net (code "109") (name "unconnected-(JP7-Pad6)") (class "Default")
      (node (ref "JP7") (pin "6") (pinfunction "6_6") (pintype "passive"))
    )
    (net (code "110") (name "unconnected-(JP7-Pad7)") (class "Default")
      (node (ref "JP7") (pin "7") (pinfunction "7_7") (pintype "passive"))
    )
    (net (code "111") (name "unconnected-(JP7-Pad8)") (class "Default")
      (node (ref "JP7") (pin "8") (pinfunction "8_8") (pintype "passive"))
    )
    (net (code "112") (name "unconnected-(JP7-Pad9)") (class "Default")
      (node (ref "JP7") (pin "9") (pinfunction "9_9") (pintype "passive"))
    )
    (net (code "113") (name "unconnected-(JP7-Pad10)") (class "Default")
      (node (ref "JP7") (pin "10") (pinfunction "10_10") (pintype "passive"))
    )
    (net (code "114") (name "unconnected-(JP9-Pad2)") (class "Default")
      (node (ref "JP9") (pin "2") (pinfunction "2_2") (pintype "passive"))
    )
    (net (code "115") (name "unconnected-(JP10-Pad2)") (class "Default")
      (node (ref "JP10") (pin "2") (pinfunction "2_2") (pintype "passive"))
    )
    (net (code "116") (name "unconnected-(JP15-Pad1)") (class "Default")
      (node (ref "JP15") (pin "1") (pinfunction "1_1") (pintype "passive"))
    )
    (net (code "117") (name "unconnected-(JP15-Pad3)") (class "Default")
      (node (ref "JP15") (pin "3") (pinfunction "3_3") (pintype "passive"))
    )
    (net (code "118") (name "unconnected-(JP15-Pad4)") (class "Default")
      (node (ref "JP15") (pin "4") (pinfunction "4_4") (pintype "passive"))
    )
    (net (code "119") (name "unconnected-(JP15-Pad5)") (class "Default")
      (node (ref "JP15") (pin "5") (pinfunction "5_5") (pintype "passive"))
    )
    (net (code "120") (name "unconnected-(JP15-Pad6)") (class "Default")
      (node (ref "JP15") (pin "6") (pinfunction "6_6") (pintype "passive"))
    )
    (net (code "121") (name "unconnected-(JP15-Pad8)") (class "Default")
      (node (ref "JP15") (pin "8") (pinfunction "8_8") (pintype "passive"))
    )
  )
)
